# DAU_Kupplung_brd_V1_7.net
KiCad netlist of a schematic drawn in EAGLE
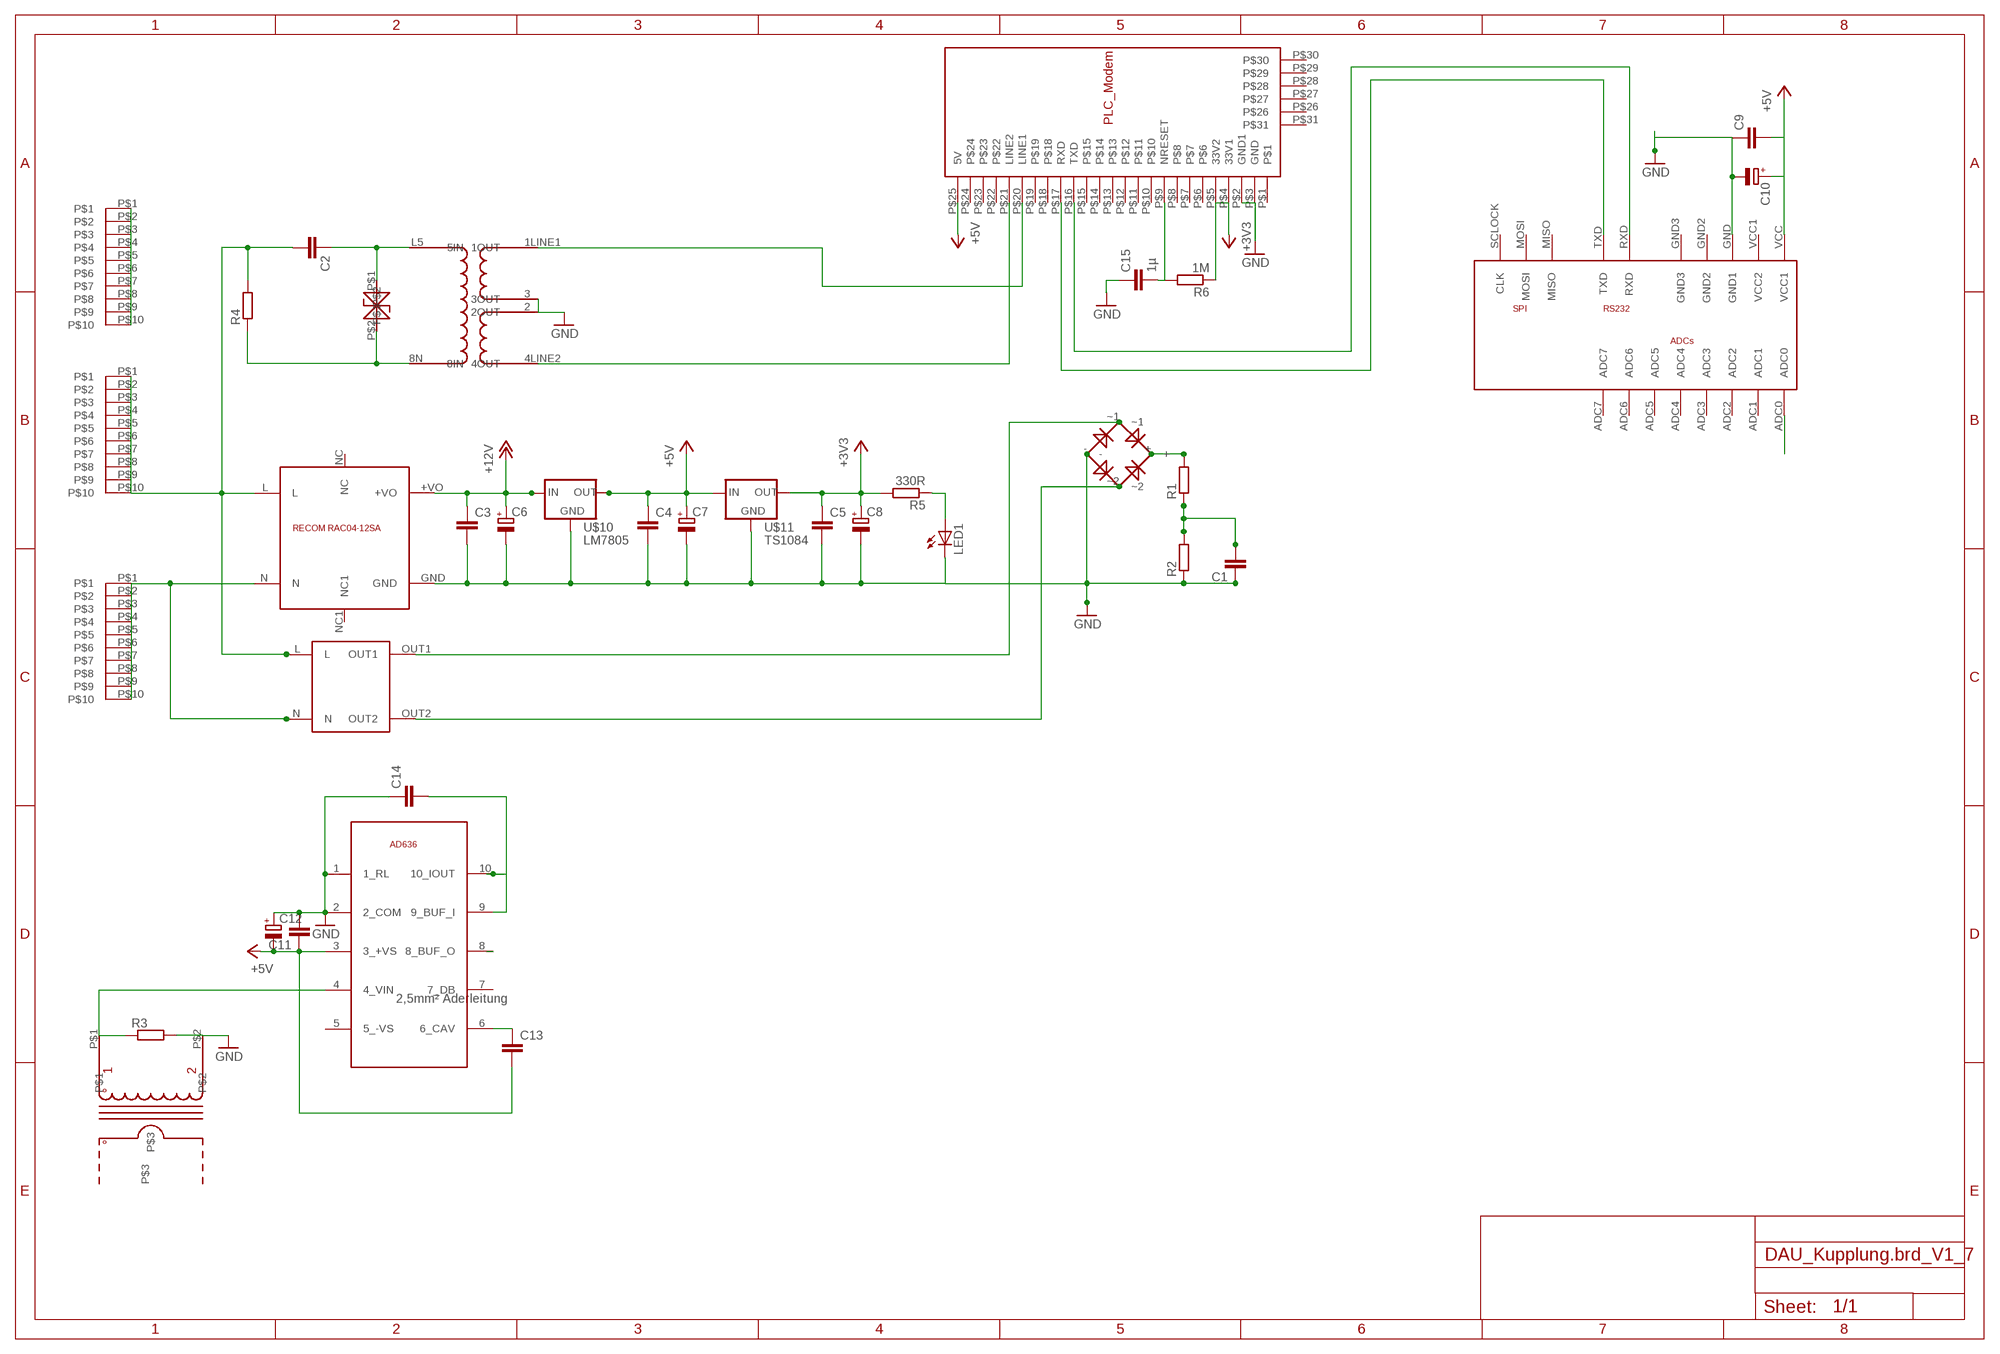
[diagram p0: schematic, sheet 1]

(export (version "E")
  (design (tool "Eeschema 10.0.6"))
  (components
    (comp (ref "C1")
      (value "C2,5-3")
      (footprint "eagle-import:C2.5-3")
      (libsource (lib "eagle-import") (part "C2,5-3"))
    )
    (comp (ref "C2")
      (value "C-EU225-087X268")
      (footprint "eagle-import:C225-087X268")
      (libsource (lib "eagle-import") (part "resistor_C-EU225-087X268"))
    )
    (comp (ref "C3")
      (value "C-EU025-040X050")
      (footprint "eagle-import:C025-040X050")
      (libsource (lib "eagle-import") (part "resistor_C-EU025-040X050"))
    )
    (comp (ref "C4")
      (value "C-EU025-040X050")
      (footprint "eagle-import:C025-040X050")
      (libsource (lib "eagle-import") (part "resistor_C-EU025-040X050"))
    )
    (comp (ref "C5")
      (value "C-EU025-040X050")
      (footprint "eagle-import:C025-040X050")
      (libsource (lib "eagle-import") (part "resistor_C-EU025-040X050"))
    )
    (comp (ref "C6")
      (value "CPOL-EUE2.5-6")
      (footprint "eagle-import:E2,5-6")
      (libsource (lib "eagle-import") (part "resistor_CPOL-EUE2.5-6"))
    )
    (comp (ref "C7")
      (value "CPOL-EUE2.5-6")
      (footprint "eagle-import:E2,5-6")
      (libsource (lib "eagle-import") (part "resistor_CPOL-EUE2.5-6"))
    )
    (comp (ref "C8")
      (value "CPOL-EUE2.5-6")
      (footprint "eagle-import:E2,5-6")
      (libsource (lib "eagle-import") (part "resistor_CPOL-EUE2.5-6"))
    )
    (comp (ref "C9")
      (value "C-EU025-040X050")
      (footprint "eagle-import:C025-040X050")
      (libsource (lib "eagle-import") (part "C-EU025-040X050"))
    )
    (comp (ref "C10")
      (value "CPOL-EUE2,5-6E")
      (footprint "eagle-import:E2,5-6E")
      (libsource (lib "eagle-import") (part "CPOL-EUE2,5-6E"))
    )
    (comp (ref "C11")
      (value "C-EU025-040X050")
      (footprint "eagle-import:C025-040X050")
      (libsource (lib "eagle-import") (part "C-EU025-040X050"))
    )
    (comp (ref "C12")
      (value "CPOL-EUE2,5-6E")
      (footprint "eagle-import:E2,5-6E")
      (libsource (lib "eagle-import") (part "CPOL-EUE2,5-6E"))
    )
    (comp (ref "C13")
      (value "C-EU025-040X050")
      (footprint "eagle-import:C025-040X050")
      (libsource (lib "eagle-import") (part "C-EU025-040X050"))
    )
    (comp (ref "C14")
      (value "C-EU025-040X050")
      (footprint "eagle-import:C025-040X050")
      (libsource (lib "eagle-import") (part "C-EU025-040X050"))
    )
    (comp (ref "C15")
      (value "1µ")
      (footprint "eagle-import:C025-040X050")
      (libsource (lib "eagle-import") (part "resistor_C-EU025-040X050"))
    )
    (comp (ref "L")
      (value "PRINT_CONNECTOR")
      (footprint "eagle-import:FASTON_DOUBLE")
      (libsource (lib "eagle-import") (part "PRINT_CONNECTOR"))
    )
    (comp (ref "LED1")
      (value "LEDSQR2X5")
      (footprint "eagle-import:LED2X5")
      (libsource (lib "eagle-import") (part "LEDSQR2X5"))
    )
    (comp (ref "N")
      (value "PRINT_CONNECTOR")
      (footprint "eagle-import:FASTON_DOUBLE")
      (libsource (lib "eagle-import") (part "PRINT_CONNECTOR"))
    )
    (comp (ref "PE")
      (value "PRINT_CONNECTOR")
      (footprint "eagle-import:FASTON_DOUBLE")
      (libsource (lib "eagle-import") (part "PRINT_CONNECTOR"))
    )
    (comp (ref "R1")
      (value "R-EU_0204/7")
      (footprint "eagle-import:0204_7")
      (libsource (lib "eagle-import") (part "R-EU_0204/7"))
    )
    (comp (ref "R2")
      (value "R-EU_0204/7")
      (footprint "eagle-import:0204_7")
      (libsource (lib "eagle-import") (part "R-EU_0204/7"))
    )
    (comp (ref "R3")
      (value "R-EU_0204/7")
      (footprint "eagle-import:0204_7")
      (libsource (lib "eagle-import") (part "R-EU_0204/7"))
    )
    (comp (ref "R4")
      (value "R-EU_0204/7")
      (footprint "eagle-import:0204_7")
      (libsource (lib "eagle-import") (part "R-EU_0204/7"))
    )
    (comp (ref "R5")
      (value "330R")
      (footprint "eagle-import:0204_7")
      (libsource (lib "eagle-import") (part "R-EU_0204/7"))
    )
    (comp (ref "R6")
      (value "1M")
      (footprint "eagle-import:0204_7")
      (libsource (lib "eagle-import") (part "R-EU_0204/7"))
    )
    (comp (ref "U$1")
      (value "RECOM_RAC04_12SA")
      (footprint "eagle-import:RAC04_12SA")
      (libsource (lib "eagle-import") (part "RECOM_RAC04_12SA"))
    )
    (comp (ref "U$2")
      (value "SICHERHEITSTRAFO")
      (footprint "eagle-import:TRAFO_0,35VA")
      (libsource (lib "eagle-import") (part "SICHERHEITSTRAFO"))
    )
    (comp (ref "U$3")
      (value "ADUC831_MINIMUM")
      (footprint "eagle-import:ADUC_MINIMUM")
      (libsource (lib "eagle-import") (part "ADUC831_MINIMUM"))
    )
    (comp (ref "U$4")
      (value "MODEMSTECKER")
      (footprint "eagle-import:MODEM_FUSS")
      (libsource (lib "eagle-import") (part "MODEMSTECKER"))
    )
    (comp (ref "U$5")
      (value "PLC_UEBERTRAGER_V2")
      (footprint "eagle-import:PLC-UEBERTRAGER_V2")
      (libsource (lib "eagle-import") (part "PLC_UEBERTRAGER_V2"))
    )
    (comp (ref "U$6")
      (value "AC1010")
      (footprint "eagle-import:AC1010")
      (libsource (lib "eagle-import") (part "AC1010"))
    )
    (comp (ref "U$7")
      (value "AD636")
      (footprint "eagle-import:TO100_10PIN")
      (libsource (lib "eagle-import") (part "AD636"))
    )
    (comp (ref "U$8")
      (value "RECTIFIER")
      (footprint "eagle-import:RECTIFIER")
      (libsource (lib "eagle-import") (part "RECTIFIER"))
    )
    (comp (ref "U$9")
      (value "SUPPRESSORDIODE15MM")
      (footprint "eagle-import:DIODE15_5MM")
      (libsource (lib "eagle-import") (part "SUPPRESSORDIODE15MM"))
    )
    (comp (ref "U$10")
      (value "LM7805")
      (footprint "eagle-import:LM7805")
      (libsource (lib "eagle-import") (part "LM7805"))
    )
    (comp (ref "U$11")
      (value "TS1084")
      (footprint "eagle-import:TS1084")
      (libsource (lib "eagle-import") (part "TS1084"))
    )
  )
  (nets
    (net (code "1") (name "+3V3") (class "Default")
      (node (ref "C5") (pin "1") (pinfunction "1_1") (pintype "passive"))
      (node (ref "C8") (pin "+") (pinfunction "+_+") (pintype "passive"))
      (node (ref "R5") (pin "2") (pinfunction "2_2") (pintype "passive"))
      (node (ref "R6") (pin "1") (pinfunction "1_1") (pintype "passive"))
      (node (ref "U$11") (pin "2OUT") (pinfunction "OUT_2OUT") (pintype "passive"))
      (node (ref "U$4") (pin "P$4") (pinfunction "33V1_P$4") (pintype "bidirectional"))
      (node (ref "U$4") (pin "P$5") (pinfunction "33V2_P$5") (pintype "bidirectional"))
    )
    (net (code "2") (name "+5V") (class "Default")
      (node (ref "C10") (pin "+") (pinfunction "+_+") (pintype "passive"))
      (node (ref "C11") (pin "1") (pinfunction "1_1") (pintype "passive"))
      (node (ref "C12") (pin "-") (pinfunction "-_-") (pintype "passive"))
      (node (ref "C13") (pin "2") (pinfunction "2_2") (pintype "passive"))
      (node (ref "C4") (pin "1") (pinfunction "1_1") (pintype "passive"))
      (node (ref "C7") (pin "+") (pinfunction "+_+") (pintype "passive"))
      (node (ref "C9") (pin "2") (pinfunction "2_2") (pintype "passive"))
      (node (ref "U$10") (pin "OUT") (pinfunction "OUT_OUT") (pintype "passive"))
      (node (ref "U$11") (pin "3IN") (pinfunction "IN_3IN") (pintype "input"))
      (node (ref "U$3") (pin "VCC") (pinfunction "VCC1_VCC") (pintype "bidirectional"))
      (node (ref "U$4") (pin "P$25") (pinfunction "5V_P$25") (pintype "bidirectional"))
      (node (ref "U$7") (pin "3") (pinfunction "3_+VS_3") (pintype "input"))
    )
    (net (code "3") (name "+12V") (class "Default")
      (node (ref "C3") (pin "1") (pinfunction "1_1") (pintype "passive"))
      (node (ref "C6") (pin "+") (pinfunction "+_+") (pintype "passive"))
      (node (ref "U$1") (pin "+VO") (pinfunction "+VO_+VO") (pintype "bidirectional"))
      (node (ref "U$10") (pin "IN") (pinfunction "IN_IN") (pintype "input"))
    )
    (net (code "4") (name "/N$6") (class "Default")
      (node (ref "C1") (pin "2") (pinfunction "2_2") (pintype "passive"))
      (node (ref "R1") (pin "1") (pinfunction "1_1") (pintype "passive"))
      (node (ref "R2") (pin "2") (pinfunction "2_2") (pintype "passive"))
      (node (ref "U$3") (pin "ADC0") (pinfunction "ADC0_ADC0") (pintype "bidirectional"))
    )
    (net (code "5") (name "GND") (class "Default")
      (node (ref "C1") (pin "1") (pinfunction "1_1") (pintype "passive"))
      (node (ref "C10") (pin "-") (pinfunction "-_-") (pintype "passive"))
      (node (ref "C11") (pin "2") (pinfunction "2_2") (pintype "passive"))
      (node (ref "C12") (pin "+") (pinfunction "+_+") (pintype "passive"))
      (node (ref "C14") (pin "1") (pinfunction "1_1") (pintype "passive"))
      (node (ref "C15") (pin "1") (pinfunction "1_1") (pintype "passive"))
      (node (ref "C3") (pin "2") (pinfunction "2_2") (pintype "passive"))
      (node (ref "C4") (pin "2") (pinfunction "2_2") (pintype "passive"))
      (node (ref "C5") (pin "2") (pinfunction "2_2") (pintype "passive"))
      (node (ref "C6") (pin "-") (pinfunction "-_-") (pintype "passive"))
      (node (ref "C7") (pin "-") (pinfunction "-_-") (pintype "passive"))
      (node (ref "C8") (pin "-") (pinfunction "-_-") (pintype "passive"))
      (node (ref "C9") (pin "1") (pinfunction "1_1") (pintype "passive"))
      (node (ref "LED1") (pin "K") (pinfunction "C_K") (pintype "passive"))
      (node (ref "R2") (pin "1") (pinfunction "1_1") (pintype "passive"))
      (node (ref "R3") (pin "2") (pinfunction "2_2") (pintype "passive"))
      (node (ref "U$1") (pin "GND") (pinfunction "GND_GND") (pintype "bidirectional"))
      (node (ref "U$10") (pin "GND") (pinfunction "GND_GND") (pintype "input"))
      (node (ref "U$11") (pin "1GND") (pinfunction "GND_1GND") (pintype "input"))
      (node (ref "U$3") (pin "GND") (pinfunction "GND1_GND") (pintype "bidirectional"))
      (node (ref "U$4") (pin "P$2") (pinfunction "GND1_P$2") (pintype "bidirectional"))
      (node (ref "U$4") (pin "P$3") (pinfunction "GND_P$3") (pintype "bidirectional"))
      (node (ref "U$5") (pin "2") (pinfunction "2OUT_2") (pintype "output"))
      (node (ref "U$5") (pin "3") (pinfunction "3OUT_3") (pintype "output"))
      (node (ref "U$6") (pin "P$2") (pinfunction "P$2_P$2") (pintype "bidirectional"))
      (node (ref "U$7") (pin "1") (pinfunction "1_RL_1") (pintype "bidirectional"))
      (node (ref "U$7") (pin "2") (pinfunction "2_COM_2") (pintype "bidirectional"))
      (node (ref "U$8") (pin "-") (pinfunction "-_-") (pintype "bidirectional"))
    )
    (net (code "6") (name "Net-(C2-Pad2)") (class "Default")
      (node (ref "C2") (pin "2") (pinfunction "2_2") (pintype "passive"))
      (node (ref "L") (pin "P$1") (pinfunction "P$1_P$1") (pintype "bidirectional"))
      (node (ref "L") (pin "P$10") (pinfunction "P$10_P$10") (pintype "bidirectional"))
      (node (ref "L") (pin "P$2") (pinfunction "P$2_P$2") (pintype "bidirectional"))
      (node (ref "L") (pin "P$3") (pinfunction "P$3_P$3") (pintype "bidirectional"))
      (node (ref "L") (pin "P$4") (pinfunction "P$4_P$4") (pintype "bidirectional"))
      (node (ref "L") (pin "P$5") (pinfunction "P$5_P$5") (pintype "bidirectional"))
      (node (ref "L") (pin "P$6") (pinfunction "P$6_P$6") (pintype "bidirectional"))
      (node (ref "L") (pin "P$7") (pinfunction "P$7_P$7") (pintype "bidirectional"))
      (node (ref "L") (pin "P$8") (pinfunction "P$8_P$8") (pintype "bidirectional"))
      (node (ref "L") (pin "P$9") (pinfunction "P$9_P$9") (pintype "bidirectional"))
      (node (ref "R4") (pin "2") (pinfunction "2_2") (pintype "passive"))
      (node (ref "U$1") (pin "L") (pinfunction "L_L") (pintype "bidirectional"))
      (node (ref "U$2") (pin "L") (pinfunction "L_L") (pintype "bidirectional"))
    )
    (net (code "7") (name "Net-(LED1-PadA)") (class "Default")
      (node (ref "LED1") (pin "A") (pinfunction "A_A") (pintype "passive"))
      (node (ref "R5") (pin "1") (pinfunction "1_1") (pintype "passive"))
    )
    (net (code "8") (name "Net-(N-PadP$1)") (class "Default")
      (node (ref "N") (pin "P$1") (pinfunction "P$1_P$1") (pintype "bidirectional"))
      (node (ref "N") (pin "P$10") (pinfunction "P$10_P$10") (pintype "bidirectional"))
      (node (ref "N") (pin "P$2") (pinfunction "P$2_P$2") (pintype "bidirectional"))
      (node (ref "N") (pin "P$3") (pinfunction "P$3_P$3") (pintype "bidirectional"))
      (node (ref "N") (pin "P$4") (pinfunction "P$4_P$4") (pintype "bidirectional"))
      (node (ref "N") (pin "P$5") (pinfunction "P$5_P$5") (pintype "bidirectional"))
      (node (ref "N") (pin "P$6") (pinfunction "P$6_P$6") (pintype "bidirectional"))
      (node (ref "N") (pin "P$7") (pinfunction "P$7_P$7") (pintype "bidirectional"))
      (node (ref "N") (pin "P$8") (pinfunction "P$8_P$8") (pintype "bidirectional"))
      (node (ref "N") (pin "P$9") (pinfunction "P$9_P$9") (pintype "bidirectional"))
      (node (ref "U$1") (pin "N") (pinfunction "N_N") (pintype "bidirectional"))
      (node (ref "U$2") (pin "N") (pinfunction "N_N") (pintype "bidirectional"))
    )
    (net (code "9") (name "Net-(PE-PadP$1)") (class "Default")
      (node (ref "PE") (pin "P$1") (pinfunction "P$1_P$1") (pintype "bidirectional"))
      (node (ref "PE") (pin "P$10") (pinfunction "P$10_P$10") (pintype "bidirectional"))
      (node (ref "PE") (pin "P$2") (pinfunction "P$2_P$2") (pintype "bidirectional"))
      (node (ref "PE") (pin "P$3") (pinfunction "P$3_P$3") (pintype "bidirectional"))
      (node (ref "PE") (pin "P$4") (pinfunction "P$4_P$4") (pintype "bidirectional"))
      (node (ref "PE") (pin "P$5") (pinfunction "P$5_P$5") (pintype "bidirectional"))
      (node (ref "PE") (pin "P$6") (pinfunction "P$6_P$6") (pintype "bidirectional"))
      (node (ref "PE") (pin "P$7") (pinfunction "P$7_P$7") (pintype "bidirectional"))
      (node (ref "PE") (pin "P$8") (pinfunction "P$8_P$8") (pintype "bidirectional"))
      (node (ref "PE") (pin "P$9") (pinfunction "P$9_P$9") (pintype "bidirectional"))
    )
    (net (code "10") (name "Net-(R1-Pad2)") (class "Default")
      (node (ref "R1") (pin "2") (pinfunction "2_2") (pintype "passive"))
      (node (ref "U$8") (pin "+") (pinfunction "+_+") (pintype "bidirectional"))
    )
    (net (code "11") (name "Net-(U$4-LINE1)") (class "Default")
      (node (ref "U$4") (pin "P$20") (pinfunction "LINE1_P$20") (pintype "bidirectional"))
      (node (ref "U$5") (pin "1LINE1") (pinfunction "1OUT_1LINE1") (pintype "output"))
    )
    (net (code "12") (name "Net-(U$4-LINE2)") (class "Default")
      (node (ref "U$4") (pin "P$21") (pinfunction "LINE2_P$21") (pintype "bidirectional"))
      (node (ref "U$5") (pin "4LINE2") (pinfunction "4OUT_4LINE2") (pintype "output"))
    )
    (net (code "13") (name "Net-(U$4-NRESET)") (class "Default")
      (node (ref "C15") (pin "2") (pinfunction "2_2") (pintype "passive"))
      (node (ref "R6") (pin "2") (pinfunction "2_2") (pintype "passive"))
      (node (ref "U$4") (pin "P$9") (pinfunction "NRESET_P$9") (pintype "bidirectional"))
    )
    (net (code "14") (name "Net-(U$4-RXD)") (class "Default")
      (node (ref "U$3") (pin "TXD") (pinfunction "TXD_TXD") (pintype "bidirectional"))
      (node (ref "U$4") (pin "P$17") (pinfunction "RXD_P$17") (pintype "bidirectional"))
    )
    (net (code "15") (name "Net-(U$4-TXD)") (class "Default")
      (node (ref "U$3") (pin "RXD") (pinfunction "RXD_RXD") (pintype "bidirectional"))
      (node (ref "U$4") (pin "P$16") (pinfunction "TXD_P$16") (pintype "bidirectional"))
    )
    (net (code "16") (name "Net-(U$5-5IN)") (class "Default")
      (node (ref "C2") (pin "1") (pinfunction "1_1") (pintype "passive"))
      (node (ref "U$5") (pin "L5") (pinfunction "5IN_L5") (pintype "input"))
      (node (ref "U$9") (pin "P$1") (pinfunction "P$1_P$1") (pintype "bidirectional"))
    )
    (net (code "17") (name "Net-(U$5-8IN)") (class "Default")
      (node (ref "R4") (pin "1") (pinfunction "1_1") (pintype "passive"))
      (node (ref "U$5") (pin "8N") (pinfunction "8IN_8N") (pintype "input"))
      (node (ref "U$9") (pin "P$2") (pinfunction "P$2_P$2") (pintype "bidirectional"))
    )
    (net (code "18") (name "Net-(U$7-4_VIN)") (class "Default")
      (node (ref "R3") (pin "1") (pinfunction "1_1") (pintype "passive"))
      (node (ref "U$6") (pin "P$1") (pinfunction "P$1_P$1") (pintype "bidirectional"))
      (node (ref "U$7") (pin "4") (pinfunction "4_VIN_4") (pintype "input"))
    )
    (net (code "19") (name "Net-(U$7-6_CAV)") (class "Default")
      (node (ref "C13") (pin "1") (pinfunction "1_1") (pintype "passive"))
      (node (ref "U$7") (pin "6") (pinfunction "6_CAV_6") (pintype "input"))
    )
    (net (code "20") (name "Net-(U$7-10_IOUT)") (class "Default")
      (node (ref "C14") (pin "2") (pinfunction "2_2") (pintype "passive"))
      (node (ref "U$7") (pin "10") (pinfunction "10_IOUT_10") (pintype "output"))
      (node (ref "U$7") (pin "9") (pinfunction "9_BUF_I_9") (pintype "input"))
    )
    (net (code "21") (name "Net-(U$8-~{1})") (class "Default")
      (node (ref "U$2") (pin "OUT1") (pinfunction "OUT1_OUT1") (pintype "bidirectional"))
      (node (ref "U$8") (pin "~1") (pinfunction "~{1}_~1") (pintype "bidirectional"))
    )
    (net (code "22") (name "Net-(U$8-~{2})") (class "Default")
      (node (ref "U$2") (pin "OUT2") (pinfunction "OUT2_OUT2") (pintype "bidirectional"))
      (node (ref "U$8") (pin "~2") (pinfunction "~{2}_~2") (pintype "bidirectional"))
    )
    (net (code "23") (name "unconnected-(U$1-PadNC)") (class "Default")
      (node (ref "U$1") (pin "NC") (pinfunction "NC_NC") (pintype "bidirectional"))
    )
    (net (code "24") (name "unconnected-(U$1-PadNC1)") (class "Default")
      (node (ref "U$1") (pin "NC1") (pinfunction "NC1_NC1") (pintype "bidirectional"))
    )
    (net (code "25") (name "unconnected-(U$3-CLK-PadSCLOCK)") (class "Default")
      (node (ref "U$3") (pin "SCLOCK") (pinfunction "CLK_SCLOCK") (pintype "bidirectional"))
    )
    (net (code "26") (name "unconnected-(U$3-PadADC1)") (class "Default")
      (node (ref "U$3") (pin "ADC1") (pinfunction "ADC1_ADC1") (pintype "bidirectional"))
    )
    (net (code "27") (name "unconnected-(U$3-PadADC2)") (class "Default")
      (node (ref "U$3") (pin "ADC2") (pinfunction "ADC2_ADC2") (pintype "bidirectional"))
    )
    (net (code "28") (name "unconnected-(U$3-PadADC3)") (class "Default")
      (node (ref "U$3") (pin "ADC3") (pinfunction "ADC3_ADC3") (pintype "bidirectional"))
    )
    (net (code "29") (name "unconnected-(U$3-PadADC4)") (class "Default")
      (node (ref "U$3") (pin "ADC4") (pinfunction "ADC4_ADC4") (pintype "bidirectional"))
    )
    (net (code "30") (name "unconnected-(U$3-PadADC5)") (class "Default")
      (node (ref "U$3") (pin "ADC5") (pinfunction "ADC5_ADC5") (pintype "bidirectional"))
    )
    (net (code "31") (name "unconnected-(U$3-PadADC6)") (class "Default")
      (node (ref "U$3") (pin "ADC6") (pinfunction "ADC6_ADC6") (pintype "bidirectional"))
    )
    (net (code "32") (name "unconnected-(U$3-PadADC7)") (class "Default")
      (node (ref "U$3") (pin "ADC7") (pinfunction "ADC7_ADC7") (pintype "bidirectional"))
    )
    (net (code "33") (name "unconnected-(U$3-PadGND2)") (class "Default")
      (node (ref "U$3") (pin "GND2") (pinfunction "GND2_GND2") (pintype "bidirectional"))
    )
    (net (code "34") (name "unconnected-(U$3-PadGND3)") (class "Default")
      (node (ref "U$3") (pin "GND3") (pinfunction "GND3_GND3") (pintype "bidirectional"))
    )
    (net (code "35") (name "unconnected-(U$3-PadMISO)") (class "Default")
      (node (ref "U$3") (pin "MISO") (pinfunction "MISO_MISO") (pintype "bidirectional"))
    )
    (net (code "36") (name "unconnected-(U$3-PadMOSI)") (class "Default")
      (node (ref "U$3") (pin "MOSI") (pinfunction "MOSI_MOSI") (pintype "bidirectional"))
    )
    (net (code "37") (name "unconnected-(U$3-VCC2-PadVCC1)") (class "Default")
      (node (ref "U$3") (pin "VCC1") (pinfunction "VCC2_VCC1") (pintype "bidirectional"))
    )
    (net (code "38") (name "unconnected-(U$4-PadP$1)") (class "Default")
      (node (ref "U$4") (pin "P$1") (pinfunction "P$1_P$1") (pintype "bidirectional"))
    )
    (net (code "39") (name "unconnected-(U$4-PadP$6)") (class "Default")
      (node (ref "U$4") (pin "P$6") (pinfunction "P$6_P$6") (pintype "bidirectional"))
    )
    (net (code "40") (name "unconnected-(U$4-PadP$7)") (class "Default")
      (node (ref "U$4") (pin "P$7") (pinfunction "P$7_P$7") (pintype "bidirectional"))
    )
    (net (code "41") (name "unconnected-(U$4-PadP$8)") (class "Default")
      (node (ref "U$4") (pin "P$8") (pinfunction "P$8_P$8") (pintype "bidirectional"))
    )
    (net (code "42") (name "unconnected-(U$4-PadP$10)") (class "Default")
      (node (ref "U$4") (pin "P$10") (pinfunction "P$10_P$10") (pintype "bidirectional"))
    )
    (net (code "43") (name "unconnected-(U$4-PadP$11)") (class "Default")
      (node (ref "U$4") (pin "P$11") (pinfunction "P$11_P$11") (pintype "bidirectional"))
    )
    (net (code "44") (name "unconnected-(U$4-PadP$12)") (class "Default")
      (node (ref "U$4") (pin "P$12") (pinfunction "P$12_P$12") (pintype "bidirectional"))
    )
    (net (code "45") (name "unconnected-(U$4-PadP$13)") (class "Default")
      (node (ref "U$4") (pin "P$13") (pinfunction "P$13_P$13") (pintype "bidirectional"))
    )
    (net (code "46") (name "unconnected-(U$4-PadP$14)") (class "Default")
      (node (ref "U$4") (pin "P$14") (pinfunction "P$14_P$14") (pintype "bidirectional"))
    )
    (net (code "47") (name "unconnected-(U$4-PadP$15)") (class "Default")
      (node (ref "U$4") (pin "P$15") (pinfunction "P$15_P$15") (pintype "bidirectional"))
    )
    (net (code "48") (name "unconnected-(U$4-PadP$18)") (class "Default")
      (node (ref "U$4") (pin "P$18") (pinfunction "P$18_P$18") (pintype "bidirectional"))
    )
    (net (code "49") (name "unconnected-(U$4-PadP$19)") (class "Default")
      (node (ref "U$4") (pin "P$19") (pinfunction "P$19_P$19") (pintype "bidirectional"))
    )
    (net (code "50") (name "unconnected-(U$4-PadP$22)") (class "Default")
      (node (ref "U$4") (pin "P$22") (pinfunction "P$22_P$22") (pintype "bidirectional"))
    )
    (net (code "51") (name "unconnected-(U$4-PadP$23)") (class "Default")
      (node (ref "U$4") (pin "P$23") (pinfunction "P$23_P$23") (pintype "bidirectional"))
    )
    (net (code "52") (name "unconnected-(U$4-PadP$24)") (class "Default")
      (node (ref "U$4") (pin "P$24") (pinfunction "P$24_P$24") (pintype "bidirectional"))
    )
    (net (code "53") (name "unconnected-(U$4-PadP$26)") (class "Default")
      (node (ref "U$4") (pin "P$26") (pinfunction "P$26_P$26") (pintype "bidirectional"))
    )
    (net (code "54") (name "unconnected-(U$4-PadP$27)") (class "Default")
      (node (ref "U$4") (pin "P$27") (pinfunction "P$27_P$27") (pintype "bidirectional"))
    )
    (net (code "55") (name "unconnected-(U$4-PadP$28)") (class "Default")
      (node (ref "U$4") (pin "P$28") (pinfunction "P$28_P$28") (pintype "bidirectional"))
    )
    (net (code "56") (name "unconnected-(U$4-PadP$29)") (class "Default")
      (node (ref "U$4") (pin "P$29") (pinfunction "P$29_P$29") (pintype "bidirectional"))
    )
    (net (code "57") (name "unconnected-(U$4-PadP$30)") (class "Default")
      (node (ref "U$4") (pin "P$30") (pinfunction "P$30_P$30") (pintype "bidirectional"))
    )
    (net (code "58") (name "unconnected-(U$4-PadP$31)") (class "Default")
      (node (ref "U$4") (pin "P$31") (pinfunction "P$31_P$31") (pintype "bidirectional"))
    )
    (net (code "59") (name "unconnected-(U$6-PadP$3)") (class "Default")
      (node (ref "U$6") (pin "P$3") (pinfunction "P$3_P$3") (pintype "bidirectional"))
    )
    (net (code "60") (name "unconnected-(U$7-5_-VS-Pad5)") (class "Default")
      (node (ref "U$7") (pin "5") (pinfunction "5_-VS_5") (pintype "input"))
    )
    (net (code "61") (name "unconnected-(U$7-7_DB-Pad7)") (class "Default")
      (node (ref "U$7") (pin "7") (pinfunction "7_DB_7") (pintype "output"))
    )
    (net (code "62") (name "unconnected-(U$7-8_BUF_O-Pad8)") (class "Default")
      (node (ref "U$7") (pin "8") (pinfunction "8_BUF_O_8") (pintype "output"))
    )
  )
)
